# 7seg.net
KiCad netlist of a schematic drawn in Altium Designer
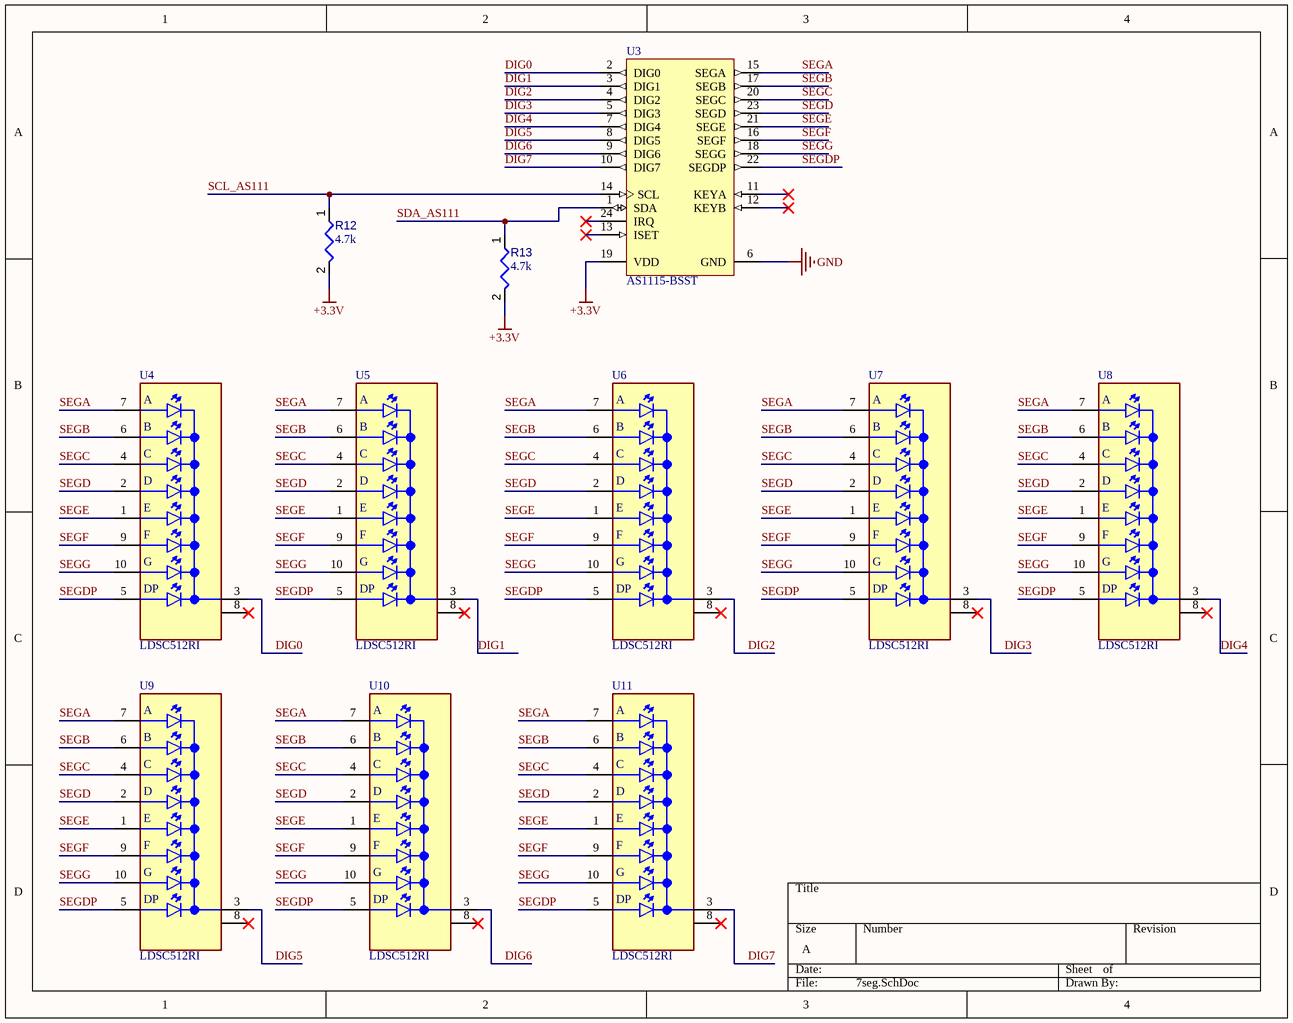
[diagram p0: 7seg.SchDoc]

(export (version "E")
  (design (tool "Eeschema 10.0.6"))
  (components
    (comp (ref "R12")
      (value "4.7k")
      (footprint "RESC0402(1005)_L")
      (description "Chip Resistor, 4,7 kOhms, +/-1 %, 63 mW, -55 to 155 degC, 0402")
      (fields (field (name "POWER") "63mW") (field (name "TOLERANCE") "1%"))
      (libsource (lib "Talha Khan") (part "RES-2"))
    )
    (comp (ref "R13")
      (value "4.7k")
      (footprint "RESC0402(1005)_L")
      (description "Chip Resistor, 4,7 kOhms, +/-1 %, 63 mW, -55 to 155 degC, 0402")
      (fields (field (name "POWER") "63mW") (field (name "TOLERANCE") "1%"))
      (libsource (lib "Talha Khan") (part "RES-2"))
    )
    (comp (ref "U3")
      (value "AS1115-BSST")
      (footprint "AMS-QSOP-24-8645X3900DE_N")
      (description "8Digits Tape & Reel (TR) 8x (7Segment) 64LED SERIAL display driver 350muA 5.5V 8.66mm -40C~85C")
      (libsource (lib "Talha Khan") (part "AMS-AS1115-QSOP-24"))
    )
    (comp (ref "U4")
      (value "LDSC512RI")
      (footprint "LED_LDSC512RI")
      (description ".56IN. 7 SEGMENT SINGLE DISPLAY, 565NM GREEN, GRAY FACE, WHITE SEGMENTS, COMMON")
      (fields (field (name "MF") "Lumex") (field (name "MP") "LDS-C512RI"))
      (libsource (lib "Talha Khan") (part "LDSC512RI"))
    )
    (comp (ref "U5")
      (value "LDSC512RI")
      (footprint "LED_LDSC512RI")
      (description ".56IN. 7 SEGMENT SINGLE DISPLAY, 565NM GREEN, GRAY FACE, WHITE SEGMENTS, COMMON")
      (fields (field (name "MF") "Lumex") (field (name "MP") "LDS-C512RI"))
      (libsource (lib "Talha Khan") (part "LDSC512RI"))
    )
    (comp (ref "U6")
      (value "LDSC512RI")
      (footprint "LED_LDSC512RI")
      (description ".56IN. 7 SEGMENT SINGLE DISPLAY, 565NM GREEN, GRAY FACE, WHITE SEGMENTS, COMMON")
      (fields (field (name "MF") "Lumex") (field (name "MP") "LDS-C512RI"))
      (libsource (lib "Talha Khan") (part "LDSC512RI"))
    )
    (comp (ref "U7")
      (value "LDSC512RI")
      (footprint "LED_LDSC512RI")
      (description ".56IN. 7 SEGMENT SINGLE DISPLAY, 565NM GREEN, GRAY FACE, WHITE SEGMENTS, COMMON")
      (fields (field (name "MF") "Lumex") (field (name "MP") "LDS-C512RI"))
      (libsource (lib "Talha Khan") (part "LDSC512RI"))
    )
    (comp (ref "U8")
      (value "LDSC512RI")
      (footprint "LED_LDSC512RI")
      (description ".56IN. 7 SEGMENT SINGLE DISPLAY, 565NM GREEN, GRAY FACE, WHITE SEGMENTS, COMMON")
      (fields (field (name "MF") "Lumex") (field (name "MP") "LDS-C512RI"))
      (libsource (lib "Talha Khan") (part "LDSC512RI"))
    )
    (comp (ref "U9")
      (value "LDSC512RI")
      (footprint "LED_LDSC512RI")
      (description ".56IN. 7 SEGMENT SINGLE DISPLAY, 565NM GREEN, GRAY FACE, WHITE SEGMENTS, COMMON")
      (fields (field (name "MF") "Lumex") (field (name "MP") "LDS-C512RI"))
      (libsource (lib "Talha Khan") (part "LDSC512RI"))
    )
    (comp (ref "U10")
      (value "LDSC512RI")
      (footprint "LED_LDSC512RI")
      (description ".56IN. 7 SEGMENT SINGLE DISPLAY, 565NM GREEN, GRAY FACE, WHITE SEGMENTS, COMMON")
      (fields (field (name "MF") "Lumex") (field (name "MP") "LDS-C512RI"))
      (libsource (lib "Talha Khan") (part "LDSC512RI"))
    )
    (comp (ref "U11")
      (value "LDSC512RI")
      (footprint "LED_LDSC512RI")
      (description ".56IN. 7 SEGMENT SINGLE DISPLAY, 565NM GREEN, GRAY FACE, WHITE SEGMENTS, COMMON")
      (fields (field (name "MF") "Lumex") (field (name "MP") "LDS-C512RI"))
      (libsource (lib "Talha Khan") (part "LDSC512RI"))
    )
  )
  (nets
    (net (code "1") (name "+3.3V") (class "Default")
      (node (ref "R12") (pin "2") (pinfunction "2_2") (pintype "passive"))
      (node (ref "R13") (pin "2") (pinfunction "2_2") (pintype "passive"))
      (node (ref "U3") (pin "19") (pinfunction "VDD_19") (pintype "power_in"))
    )
    (net (code "2") (name "/DIG0") (class "Default")
      (node (ref "U3") (pin "2") (pinfunction "DIG0_2") (pintype "output"))
      (node (ref "U4") (pin "3") (pinfunction "CC_3") (pintype "passive"))
    )
    (net (code "3") (name "/DIG1") (class "Default")
      (node (ref "U3") (pin "3") (pinfunction "DIG1_3") (pintype "output"))
      (node (ref "U5") (pin "3") (pinfunction "CC_3") (pintype "passive"))
    )
    (net (code "4") (name "/DIG2") (class "Default")
      (node (ref "U3") (pin "4") (pinfunction "DIG2_4") (pintype "output"))
      (node (ref "U6") (pin "3") (pinfunction "CC_3") (pintype "passive"))
    )
    (net (code "5") (name "/DIG3") (class "Default")
      (node (ref "U3") (pin "5") (pinfunction "DIG3_5") (pintype "output"))
      (node (ref "U7") (pin "3") (pinfunction "CC_3") (pintype "passive"))
    )
    (net (code "6") (name "/DIG4") (class "Default")
      (node (ref "U3") (pin "7") (pinfunction "DIG4_7") (pintype "output"))
      (node (ref "U8") (pin "3") (pinfunction "CC_3") (pintype "passive"))
    )
    (net (code "7") (name "/DIG5") (class "Default")
      (node (ref "U3") (pin "8") (pinfunction "DIG5_8") (pintype "output"))
      (node (ref "U9") (pin "3") (pinfunction "CC_3") (pintype "passive"))
    )
    (net (code "8") (name "/DIG6") (class "Default")
      (node (ref "U10") (pin "3") (pinfunction "CC_3") (pintype "passive"))
      (node (ref "U3") (pin "9") (pinfunction "DIG6_9") (pintype "output"))
    )
    (net (code "9") (name "/DIG7") (class "Default")
      (node (ref "U11") (pin "3") (pinfunction "CC_3") (pintype "passive"))
      (node (ref "U3") (pin "10") (pinfunction "DIG7_10") (pintype "output"))
    )
    (net (code "10") (name "/SCL_AS111") (class "Default")
      (node (ref "R12") (pin "1") (pinfunction "1_1") (pintype "passive"))
      (node (ref "U3") (pin "14") (pinfunction "SCL_14") (pintype "input"))
    )
    (net (code "11") (name "/SDA_AS111") (class "Default")
      (node (ref "R13") (pin "1") (pinfunction "1_1") (pintype "passive"))
      (node (ref "U3") (pin "1") (pinfunction "SDA_1") (pintype "bidirectional"))
    )
    (net (code "12") (name "/SEGA") (class "Default")
      (node (ref "U10") (pin "7") (pinfunction "A_7") (pintype "passive"))
      (node (ref "U11") (pin "7") (pinfunction "A_7") (pintype "passive"))
      (node (ref "U3") (pin "15") (pinfunction "SEGA_15") (pintype "output"))
      (node (ref "U4") (pin "7") (pinfunction "A_7") (pintype "passive"))
      (node (ref "U5") (pin "7") (pinfunction "A_7") (pintype "passive"))
      (node (ref "U6") (pin "7") (pinfunction "A_7") (pintype "passive"))
      (node (ref "U7") (pin "7") (pinfunction "A_7") (pintype "passive"))
      (node (ref "U8") (pin "7") (pinfunction "A_7") (pintype "passive"))
      (node (ref "U9") (pin "7") (pinfunction "A_7") (pintype "passive"))
    )
    (net (code "13") (name "/SEGB") (class "Default")
      (node (ref "U10") (pin "6") (pinfunction "B_6") (pintype "passive"))
      (node (ref "U11") (pin "6") (pinfunction "B_6") (pintype "passive"))
      (node (ref "U3") (pin "17") (pinfunction "SEGB_17") (pintype "output"))
      (node (ref "U4") (pin "6") (pinfunction "B_6") (pintype "passive"))
      (node (ref "U5") (pin "6") (pinfunction "B_6") (pintype "passive"))
      (node (ref "U6") (pin "6") (pinfunction "B_6") (pintype "passive"))
      (node (ref "U7") (pin "6") (pinfunction "B_6") (pintype "passive"))
      (node (ref "U8") (pin "6") (pinfunction "B_6") (pintype "passive"))
      (node (ref "U9") (pin "6") (pinfunction "B_6") (pintype "passive"))
    )
    (net (code "14") (name "/SEGC") (class "Default")
      (node (ref "U10") (pin "4") (pinfunction "C_4") (pintype "passive"))
      (node (ref "U11") (pin "4") (pinfunction "C_4") (pintype "passive"))
      (node (ref "U3") (pin "20") (pinfunction "SEGC_20") (pintype "output"))
      (node (ref "U4") (pin "4") (pinfunction "C_4") (pintype "passive"))
      (node (ref "U5") (pin "4") (pinfunction "C_4") (pintype "passive"))
      (node (ref "U6") (pin "4") (pinfunction "C_4") (pintype "passive"))
      (node (ref "U7") (pin "4") (pinfunction "C_4") (pintype "passive"))
      (node (ref "U8") (pin "4") (pinfunction "C_4") (pintype "passive"))
      (node (ref "U9") (pin "4") (pinfunction "C_4") (pintype "passive"))
    )
    (net (code "15") (name "/SEGD") (class "Default")
      (node (ref "U10") (pin "2") (pinfunction "D_2") (pintype "passive"))
      (node (ref "U11") (pin "2") (pinfunction "D_2") (pintype "passive"))
      (node (ref "U3") (pin "23") (pinfunction "SEGD_23") (pintype "output"))
      (node (ref "U4") (pin "2") (pinfunction "D_2") (pintype "passive"))
      (node (ref "U5") (pin "2") (pinfunction "D_2") (pintype "passive"))
      (node (ref "U6") (pin "2") (pinfunction "D_2") (pintype "passive"))
      (node (ref "U7") (pin "2") (pinfunction "D_2") (pintype "passive"))
      (node (ref "U8") (pin "2") (pinfunction "D_2") (pintype "passive"))
      (node (ref "U9") (pin "2") (pinfunction "D_2") (pintype "passive"))
    )
    (net (code "16") (name "/SEGDP") (class "Default")
      (node (ref "U10") (pin "5") (pinfunction "DP_5") (pintype "passive"))
      (node (ref "U11") (pin "5") (pinfunction "DP_5") (pintype "passive"))
      (node (ref "U3") (pin "22") (pinfunction "SEGDP_22") (pintype "output"))
      (node (ref "U4") (pin "5") (pinfunction "DP_5") (pintype "passive"))
      (node (ref "U5") (pin "5") (pinfunction "DP_5") (pintype "passive"))
      (node (ref "U6") (pin "5") (pinfunction "DP_5") (pintype "passive"))
      (node (ref "U7") (pin "5") (pinfunction "DP_5") (pintype "passive"))
      (node (ref "U8") (pin "5") (pinfunction "DP_5") (pintype "passive"))
      (node (ref "U9") (pin "5") (pinfunction "DP_5") (pintype "passive"))
    )
    (net (code "17") (name "/SEGE") (class "Default")
      (node (ref "U10") (pin "1") (pinfunction "E_1") (pintype "passive"))
      (node (ref "U11") (pin "1") (pinfunction "E_1") (pintype "passive"))
      (node (ref "U3") (pin "21") (pinfunction "SEGE_21") (pintype "output"))
      (node (ref "U4") (pin "1") (pinfunction "E_1") (pintype "passive"))
      (node (ref "U5") (pin "1") (pinfunction "E_1") (pintype "passive"))
      (node (ref "U6") (pin "1") (pinfunction "E_1") (pintype "passive"))
      (node (ref "U7") (pin "1") (pinfunction "E_1") (pintype "passive"))
      (node (ref "U8") (pin "1") (pinfunction "E_1") (pintype "passive"))
      (node (ref "U9") (pin "1") (pinfunction "E_1") (pintype "passive"))
    )
    (net (code "18") (name "/SEGF") (class "Default")
      (node (ref "U10") (pin "9") (pinfunction "F_9") (pintype "passive"))
      (node (ref "U11") (pin "9") (pinfunction "F_9") (pintype "passive"))
      (node (ref "U3") (pin "16") (pinfunction "SEGF_16") (pintype "output"))
      (node (ref "U4") (pin "9") (pinfunction "F_9") (pintype "passive"))
      (node (ref "U5") (pin "9") (pinfunction "F_9") (pintype "passive"))
      (node (ref "U6") (pin "9") (pinfunction "F_9") (pintype "passive"))
      (node (ref "U7") (pin "9") (pinfunction "F_9") (pintype "passive"))
      (node (ref "U8") (pin "9") (pinfunction "F_9") (pintype "passive"))
      (node (ref "U9") (pin "9") (pinfunction "F_9") (pintype "passive"))
    )
    (net (code "19") (name "/SEGG") (class "Default")
      (node (ref "U10") (pin "10") (pinfunction "G_10") (pintype "passive"))
      (node (ref "U11") (pin "10") (pinfunction "G_10") (pintype "passive"))
      (node (ref "U3") (pin "18") (pinfunction "SEGG_18") (pintype "output"))
      (node (ref "U4") (pin "10") (pinfunction "G_10") (pintype "passive"))
      (node (ref "U5") (pin "10") (pinfunction "G_10") (pintype "passive"))
      (node (ref "U6") (pin "10") (pinfunction "G_10") (pintype "passive"))
      (node (ref "U7") (pin "10") (pinfunction "G_10") (pintype "passive"))
      (node (ref "U8") (pin "10") (pinfunction "G_10") (pintype "passive"))
      (node (ref "U9") (pin "10") (pinfunction "G_10") (pintype "passive"))
    )
    (net (code "20") (name "GND") (class "Default")
      (node (ref "U3") (pin "6") (pinfunction "GND_6") (pintype "power_in"))
    )
    (net (code "21") (name "unconnected-(U3-IRQ-Pad24)") (class "Default")
      (node (ref "U3") (pin "24") (pinfunction "IRQ_24") (pintype "tri_state+no_connect"))
    )
    (net (code "22") (name "unconnected-(U3-ISET-Pad13)") (class "Default")
      (node (ref "U3") (pin "13") (pinfunction "ISET_13") (pintype "input+no_connect"))
    )
    (net (code "23") (name "unconnected-(U3-KEYA-Pad11)") (class "Default")
      (node (ref "U3") (pin "11") (pinfunction "KEYA_11") (pintype "input+no_connect"))
    )
    (net (code "24") (name "unconnected-(U3-KEYB-Pad12)") (class "Default")
      (node (ref "U3") (pin "12") (pinfunction "KEYB_12") (pintype "input+no_connect"))
    )
    (net (code "25") (name "unconnected-(U4-CC-Pad8)") (class "Default")
      (node (ref "U4") (pin "8") (pinfunction "CC_8") (pintype "passive+no_connect"))
    )
    (net (code "26") (name "unconnected-(U5-CC-Pad8)") (class "Default")
      (node (ref "U5") (pin "8") (pinfunction "CC_8") (pintype "passive+no_connect"))
    )
    (net (code "27") (name "unconnected-(U6-CC-Pad8)") (class "Default")
      (node (ref "U6") (pin "8") (pinfunction "CC_8") (pintype "passive+no_connect"))
    )
    (net (code "28") (name "unconnected-(U7-CC-Pad8)") (class "Default")
      (node (ref "U7") (pin "8") (pinfunction "CC_8") (pintype "passive+no_connect"))
    )
    (net (code "29") (name "unconnected-(U8-CC-Pad8)") (class "Default")
      (node (ref "U8") (pin "8") (pinfunction "CC_8") (pintype "passive+no_connect"))
    )
    (net (code "30") (name "unconnected-(U9-CC-Pad8)") (class "Default")
      (node (ref "U9") (pin "8") (pinfunction "CC_8") (pintype "passive+no_connect"))
    )
    (net (code "31") (name "unconnected-(U10-CC-Pad8)") (class "Default")
      (node (ref "U10") (pin "8") (pinfunction "CC_8") (pintype "passive+no_connect"))
    )
    (net (code "32") (name "unconnected-(U11-CC-Pad8)") (class "Default")
      (node (ref "U11") (pin "8") (pinfunction "CC_8") (pintype "passive+no_connect"))
    )
  )
)
